# BASE_1.net
KiCad netlist of a schematic drawn in Altium Designer
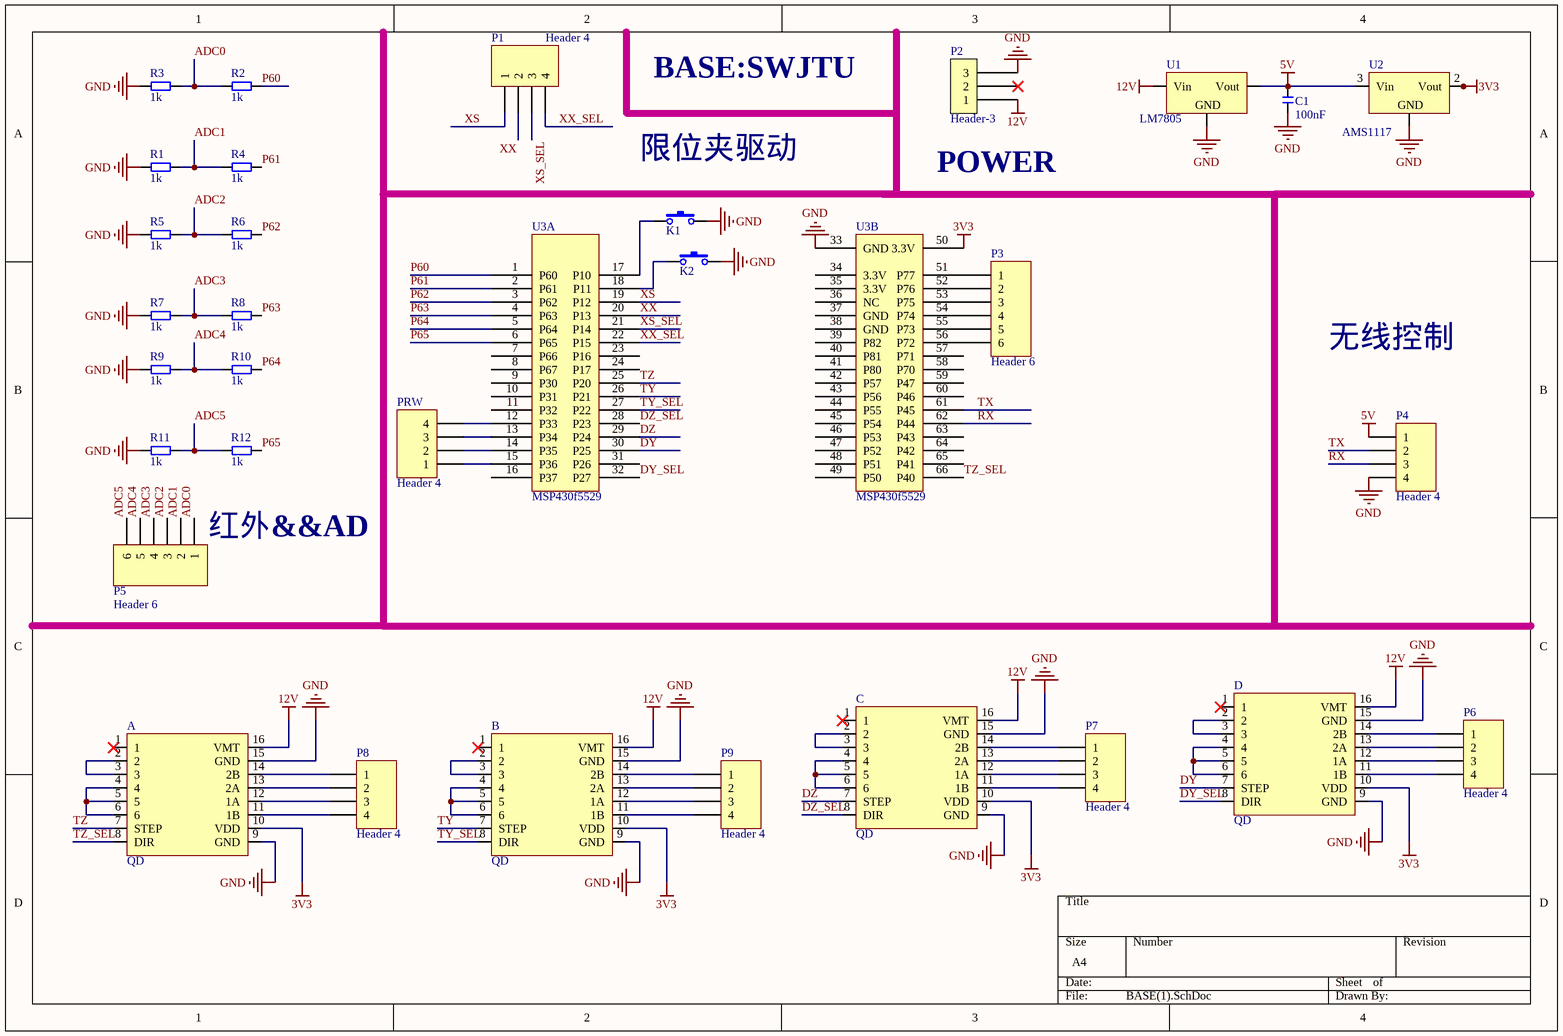
[diagram p0: BASE(1).SchDoc]

(export (version "E")
  (design (tool "Eeschema 10.0.6"))
  (components
    (comp (ref "A") (value "QD") (footprint "QD") (libsource (lib "QD") (part "QD")))
    (comp (ref "B") (value "QD") (footprint "QD") (libsource (lib "QD") (part "QD")))
    (comp (ref "C") (value "QD") (footprint "QD") (libsource (lib "QD") (part "QD")))
    (comp (ref "C1")
      (value "100nF")
      (footprint "lanfengdi:CAP-7.6")
      (description "无极电容")
      (libsource (lib "lanfengdi") (part "Cap"))
    )
    (comp (ref "D") (value "QD") (footprint "QD") (libsource (lib "QD") (part "QD")))
    (comp (ref "K1")
      (value "SW-PB")
      (footprint "lanfengdi:SW-4")
      (description "轻触开关")
      (libsource (lib "lanfengdi") (part "SW-PB"))
    )
    (comp (ref "K2")
      (value "SW-PB")
      (footprint "lanfengdi:SW-4")
      (description "轻触开关")
      (libsource (lib "lanfengdi") (part "SW-PB"))
    )
    (comp (ref "P1")
      (value "Header 4")
      (footprint "4PIN-2.54 A")
      (description "Header, 4-Pin")
      (fields (field (name "PUBLISHER") "Altium Limited"))
      (libsource (lib "") (part "Header 4_1"))
    )
    (comp (ref "P2")
      (value "Header-3")
      (footprint "terminal-03-3")
      (description "三针插座")
      (libsource (lib "Connection") (part "Header-3"))
    )
    (comp (ref "P3")
      (value "Header 6")
      (footprint "HDR1X6")
      (description "Header, 6-Pin")
      (fields (field (name "PUBLISHER") "Altium Limited"))
      (libsource (lib "") (part "Header 6_1"))
    )
    (comp (ref "P4")
      (value "Header 4")
      (footprint "4PIN-2.54 A")
      (description "Header, 4-Pin")
      (fields (field (name "PUBLISHER") "Altium Limited"))
      (libsource (lib "Miscellaneous Connectors") (part "Header 4"))
    )
    (comp (ref "P5")
      (value "Header 6")
      (footprint "HDR1X6")
      (description "Header, 6-Pin")
      (fields (field (name "PUBLISHER") "Altium Limited"))
      (libsource (lib "Miscellaneous Connectors") (part "Header 6"))
    )
    (comp (ref "P6")
      (value "Header 4")
      (footprint "4PIN-2.54 A")
      (description "Header, 4-Pin")
      (fields (field (name "PUBLISHER") "Altium Limited"))
      (libsource (lib "Miscellaneous Connectors") (part "Header 4"))
    )
    (comp (ref "P7")
      (value "Header 4")
      (footprint "4PIN-2.54 A")
      (description "Header, 4-Pin")
      (fields (field (name "PUBLISHER") "Altium Limited"))
      (libsource (lib "Miscellaneous Connectors") (part "Header 4"))
    )
    (comp (ref "P8")
      (value "Header 4")
      (footprint "4PIN-2.54 A")
      (description "Header, 4-Pin")
      (fields (field (name "PUBLISHER") "Altium Limited"))
      (libsource (lib "Miscellaneous Connectors") (part "Header 4"))
    )
    (comp (ref "P9")
      (value "Header 4")
      (footprint "4PIN-2.54 A")
      (description "Header, 4-Pin")
      (fields (field (name "PUBLISHER") "Altium Limited"))
      (libsource (lib "Miscellaneous Connectors") (part "Header 4"))
    )
    (comp (ref "PRW")
      (value "Header 4")
      (footprint "4PIN-2.54 A")
      (description "Header, 4-Pin")
      (fields (field (name "PUBLISHER") "Altium Limited"))
      (libsource (lib "") (part "Header 4_2"))
    )
    (comp (ref "R1")
      (value "1k")
      (footprint "Axial-0.3-7.62")
      (description "电阻  RES")
      (libsource (lib "lanfengdi") (part "RES"))
    )
    (comp (ref "R2")
      (value "1k")
      (footprint "lanfengdi:R0805")
      (description "电阻  RES")
      (libsource (lib "lanfengdi") (part "RES"))
    )
    (comp (ref "R3")
      (value "1k")
      (footprint "lanfengdi:R0805")
      (description "电阻  RES")
      (libsource (lib "lanfengdi") (part "RES"))
    )
    (comp (ref "R4")
      (value "1k")
      (footprint "lanfengdi:R0805")
      (description "电阻  RES")
      (libsource (lib "lanfengdi") (part "RES"))
    )
    (comp (ref "R5")
      (value "1k")
      (footprint "Axial-0.3-7.62")
      (description "电阻  RES")
      (libsource (lib "lanfengdi") (part "RES"))
    )
    (comp (ref "R6")
      (value "1k")
      (footprint "lanfengdi:R0805")
      (description "电阻  RES")
      (libsource (lib "lanfengdi") (part "RES"))
    )
    (comp (ref "R7")
      (value "1k")
      (footprint "Axial-0.3-7.62")
      (description "电阻  RES")
      (libsource (lib "lanfengdi") (part "RES"))
    )
    (comp (ref "R8")
      (value "1k")
      (footprint "lanfengdi:R0805")
      (description "电阻  RES")
      (libsource (lib "lanfengdi") (part "RES"))
    )
    (comp (ref "R9")
      (value "1k")
      (footprint "Axial-0.3-7.62")
      (description "电阻  RES")
      (libsource (lib "lanfengdi") (part "RES"))
    )
    (comp (ref "R10")
      (value "1k")
      (footprint "lanfengdi:R0805")
      (description "电阻  RES")
      (libsource (lib "lanfengdi") (part "RES"))
    )
    (comp (ref "R11")
      (value "1k")
      (footprint "lanfengdi:R0805")
      (description "电阻  RES")
      (libsource (lib "lanfengdi") (part "RES"))
    )
    (comp (ref "R12")
      (value "1k")
      (footprint "lanfengdi:R0805")
      (description "电阻  RES")
      (libsource (lib "lanfengdi") (part "RES"))
    )
    (comp (ref "U1")
      (value "LM7805")
      (footprint "lanfengdi:TO-220")
      (description "三端稳压器")
      (libsource (lib "lanfengdi") (part "LM78XX"))
    )
    (comp (ref "U2")
      (value "AMS1117")
      (footprint "lanfengdi:SOT-223")
      (description "LDO")
      (libsource (lib "lanfengdi") (part "AMS1117"))
    )
    (comp (ref "U3")
      (value "MSP430f5529")
      (footprint "msp430f5529")
      (libsource (lib "5529") (part "MSP430f5529"))
    )
  )
  (nets
    (net (code "1") (name "/ADC0") (class "Default")
      (node (ref "P5") (pin "1") (pinfunction "1_1") (pintype "passive"))
      (node (ref "R2") (pin "1") (pinfunction "1_1") (pintype "passive"))
      (node (ref "R3") (pin "2") (pinfunction "2_2") (pintype "passive"))
    )
    (net (code "2") (name "/ADC1") (class "Default")
      (node (ref "P5") (pin "2") (pinfunction "2_2") (pintype "passive"))
      (node (ref "R1") (pin "2") (pinfunction "2_2") (pintype "passive"))
      (node (ref "R4") (pin "1") (pinfunction "1_1") (pintype "passive"))
    )
    (net (code "3") (name "/ADC2") (class "Default")
      (node (ref "P5") (pin "3") (pinfunction "3_3") (pintype "passive"))
      (node (ref "R5") (pin "2") (pinfunction "2_2") (pintype "passive"))
      (node (ref "R6") (pin "1") (pinfunction "1_1") (pintype "passive"))
    )
    (net (code "4") (name "/ADC3") (class "Default")
      (node (ref "P5") (pin "4") (pinfunction "4_4") (pintype "passive"))
      (node (ref "R7") (pin "2") (pinfunction "2_2") (pintype "passive"))
      (node (ref "R8") (pin "1") (pinfunction "1_1") (pintype "passive"))
    )
    (net (code "5") (name "/ADC4") (class "Default")
      (node (ref "P5") (pin "5") (pinfunction "5_5") (pintype "passive"))
      (node (ref "R10") (pin "1") (pinfunction "1_1") (pintype "passive"))
      (node (ref "R9") (pin "2") (pinfunction "2_2") (pintype "passive"))
    )
    (net (code "6") (name "/ADC5") (class "Default")
      (node (ref "P5") (pin "6") (pinfunction "6_6") (pintype "passive"))
      (node (ref "R11") (pin "2") (pinfunction "2_2") (pintype "passive"))
      (node (ref "R12") (pin "1") (pinfunction "1_1") (pintype "passive"))
    )
    (net (code "7") (name "/DY") (class "Default")
      (node (ref "D") (pin "7") (pinfunction "STEP_7") (pintype "passive"))
      (node (ref "U3") (pin "30") (pinfunction "P25_30") (pintype "passive"))
    )
    (net (code "8") (name "/DY_SEL") (class "Default")
      (node (ref "D") (pin "8") (pinfunction "DIR_8") (pintype "passive"))
      (node (ref "U3") (pin "32") (pinfunction "P27_32") (pintype "passive"))
    )
    (net (code "9") (name "/DZ") (class "Default")
      (node (ref "C") (pin "7") (pinfunction "STEP_7") (pintype "passive"))
      (node (ref "U3") (pin "29") (pinfunction "P24_29") (pintype "passive"))
    )
    (net (code "10") (name "/DZ_SEL") (class "Default")
      (node (ref "C") (pin "8") (pinfunction "DIR_8") (pintype "passive"))
      (node (ref "U3") (pin "28") (pinfunction "P23_28") (pintype "passive"))
    )
    (net (code "11") (name "/P60") (class "Default")
      (node (ref "R2") (pin "2") (pinfunction "2_2") (pintype "passive"))
      (node (ref "U3") (pin "1") (pinfunction "P60_1") (pintype "passive"))
    )
    (net (code "12") (name "/P61") (class "Default")
      (node (ref "R4") (pin "2") (pinfunction "2_2") (pintype "passive"))
      (node (ref "U3") (pin "2") (pinfunction "P61_2") (pintype "passive"))
    )
    (net (code "13") (name "/P62") (class "Default")
      (node (ref "R6") (pin "2") (pinfunction "2_2") (pintype "passive"))
      (node (ref "U3") (pin "3") (pinfunction "P62_3") (pintype "passive"))
    )
    (net (code "14") (name "/P63") (class "Default")
      (node (ref "R8") (pin "2") (pinfunction "2_2") (pintype "passive"))
      (node (ref "U3") (pin "4") (pinfunction "P63_4") (pintype "passive"))
    )
    (net (code "15") (name "/P64") (class "Default")
      (node (ref "R10") (pin "2") (pinfunction "2_2") (pintype "passive"))
      (node (ref "U3") (pin "5") (pinfunction "P64_5") (pintype "passive"))
    )
    (net (code "16") (name "/P65") (class "Default")
      (node (ref "R12") (pin "2") (pinfunction "2_2") (pintype "passive"))
      (node (ref "U3") (pin "6") (pinfunction "P65_6") (pintype "passive"))
    )
    (net (code "17") (name "/RX") (class "Default")
      (node (ref "P4") (pin "3") (pinfunction "3_3") (pintype "passive"))
      (node (ref "U3") (pin "62") (pinfunction "P44_62") (pintype "passive"))
    )
    (net (code "18") (name "/TX") (class "Default")
      (node (ref "P4") (pin "2") (pinfunction "2_2") (pintype "passive"))
      (node (ref "U3") (pin "61") (pinfunction "P45_61") (pintype "passive"))
    )
    (net (code "19") (name "/TY") (class "Default")
      (node (ref "B") (pin "7") (pinfunction "STEP_7") (pintype "passive"))
      (node (ref "U3") (pin "26") (pinfunction "P21_26") (pintype "passive"))
    )
    (net (code "20") (name "/TY_SEL") (class "Default")
      (node (ref "B") (pin "8") (pinfunction "DIR_8") (pintype "passive"))
      (node (ref "U3") (pin "27") (pinfunction "P22_27") (pintype "passive"))
    )
    (net (code "21") (name "/TZ") (class "Default")
      (node (ref "A") (pin "7") (pinfunction "STEP_7") (pintype "passive"))
      (node (ref "U3") (pin "25") (pinfunction "P20_25") (pintype "passive"))
    )
    (net (code "22") (name "/TZ_SEL") (class "Default")
      (node (ref "A") (pin "8") (pinfunction "DIR_8") (pintype "passive"))
      (node (ref "U3") (pin "66") (pinfunction "P40_66") (pintype "passive"))
    )
    (net (code "23") (name "/XS") (class "Default")
      (node (ref "P1") (pin "1") (pinfunction "1_1") (pintype "passive"))
      (node (ref "U3") (pin "19") (pinfunction "P12_19") (pintype "passive"))
    )
    (net (code "24") (name "/XS_SEL") (class "Default")
      (node (ref "P1") (pin "3") (pinfunction "3_3") (pintype "passive"))
      (node (ref "U3") (pin "21") (pinfunction "P14_21") (pintype "passive"))
    )
    (net (code "25") (name "/XX") (class "Default")
      (node (ref "P1") (pin "2") (pinfunction "2_2") (pintype "passive"))
      (node (ref "U3") (pin "20") (pinfunction "P13_20") (pintype "passive"))
    )
    (net (code "26") (name "/XX_SEL") (class "Default")
      (node (ref "P1") (pin "4") (pinfunction "4_4") (pintype "passive"))
      (node (ref "U3") (pin "22") (pinfunction "P15_22") (pintype "passive"))
    )
    (net (code "27") (name "3V3") (class "Default")
      (node (ref "A") (pin "10") (pinfunction "VDD_10") (pintype "passive"))
      (node (ref "B") (pin "10") (pinfunction "VDD_10") (pintype "passive"))
      (node (ref "C") (pin "10") (pinfunction "VDD_10") (pintype "passive"))
      (node (ref "D") (pin "10") (pinfunction "VDD_10") (pintype "passive"))
      (node (ref "U2") (pin "2") (pinfunction "Vout_2") (pintype "passive"))
      (node (ref "U2") (pin "4") (pinfunction "Vout_4") (pintype "passive"))
      (node (ref "U3") (pin "50") (pinfunction "3.3V_50") (pintype "passive"))
    )
    (net (code "28") (name "5V") (class "Default")
      (node (ref "C1") (pin "2") (pinfunction "2_2") (pintype "passive"))
      (node (ref "P4") (pin "1") (pinfunction "1_1") (pintype "passive"))
      (node (ref "U1") (pin "3") (pinfunction "Vout_3") (pintype "passive"))
      (node (ref "U2") (pin "3") (pinfunction "Vin_3") (pintype "passive"))
    )
    (net (code "29") (name "12V") (class "Default")
      (node (ref "A") (pin "16") (pinfunction "VMT_16") (pintype "passive"))
      (node (ref "B") (pin "16") (pinfunction "VMT_16") (pintype "passive"))
      (node (ref "C") (pin "16") (pinfunction "VMT_16") (pintype "passive"))
      (node (ref "D") (pin "16") (pinfunction "VMT_16") (pintype "passive"))
      (node (ref "P2") (pin "1") (pinfunction "1_1") (pintype "passive"))
      (node (ref "U1") (pin "1") (pinfunction "Vin_1") (pintype "passive"))
    )
    (net (code "30") (name "GND") (class "Default")
      (node (ref "A") (pin "15") (pinfunction "GND_15") (pintype "passive"))
      (node (ref "A") (pin "9") (pinfunction "GND_9") (pintype "passive"))
      (node (ref "B") (pin "15") (pinfunction "GND_15") (pintype "passive"))
      (node (ref "B") (pin "9") (pinfunction "GND_9") (pintype "passive"))
      (node (ref "C") (pin "15") (pinfunction "GND_15") (pintype "passive"))
      (node (ref "C") (pin "9") (pinfunction "GND_9") (pintype "passive"))
      (node (ref "C1") (pin "1") (pinfunction "1_1") (pintype "passive"))
      (node (ref "D") (pin "15") (pinfunction "GND_15") (pintype "passive"))
      (node (ref "D") (pin "9") (pinfunction "GND_9") (pintype "passive"))
      (node (ref "K1") (pin "2") (pinfunction "2_2") (pintype "passive"))
      (node (ref "K2") (pin "2") (pinfunction "2_2") (pintype "passive"))
      (node (ref "P2") (pin "3") (pinfunction "3_3") (pintype "passive"))
      (node (ref "P4") (pin "4") (pinfunction "4_4") (pintype "passive"))
      (node (ref "R1") (pin "1") (pinfunction "1_1") (pintype "passive"))
      (node (ref "R11") (pin "1") (pinfunction "1_1") (pintype "passive"))
      (node (ref "R3") (pin "1") (pinfunction "1_1") (pintype "passive"))
      (node (ref "R5") (pin "1") (pinfunction "1_1") (pintype "passive"))
      (node (ref "R7") (pin "1") (pinfunction "1_1") (pintype "passive"))
      (node (ref "R9") (pin "1") (pinfunction "1_1") (pintype "passive"))
      (node (ref "U1") (pin "2") (pinfunction "GND_2") (pintype "passive"))
      (node (ref "U2") (pin "1") (pinfunction "GND_1") (pintype "passive"))
      (node (ref "U3") (pin "33") (pinfunction "GND_33") (pintype "passive"))
    )
    (net (code "31") (name "Net-(A-1A)") (class "Default")
      (node (ref "A") (pin "12") (pinfunction "1A_12") (pintype "passive"))
      (node (ref "P8") (pin "3") (pinfunction "3_3") (pintype "passive"))
    )
    (net (code "32") (name "Net-(A-1B)") (class "Default")
      (node (ref "A") (pin "11") (pinfunction "1B_11") (pintype "passive"))
      (node (ref "P8") (pin "4") (pinfunction "4_4") (pintype "passive"))
    )
    (net (code "33") (name "Net-(A-2A)") (class "Default")
      (node (ref "A") (pin "13") (pinfunction "2A_13") (pintype "passive"))
      (node (ref "P8") (pin "2") (pinfunction "2_2") (pintype "passive"))
    )
    (net (code "34") (name "Net-(A-2B)") (class "Default")
      (node (ref "A") (pin "14") (pinfunction "2B_14") (pintype "passive"))
      (node (ref "P8") (pin "1") (pinfunction "1_1") (pintype "passive"))
    )
    (net (code "35") (name "Net-(A-Pad2)") (class "Default")
      (node (ref "A") (pin "2") (pinfunction "2_2") (pintype "passive"))
      (node (ref "A") (pin "3") (pinfunction "3_3") (pintype "passive"))
    )
    (net (code "36") (name "Net-(A-Pad4)") (class "Default")
      (node (ref "A") (pin "4") (pinfunction "4_4") (pintype "passive"))
      (node (ref "A") (pin "5") (pinfunction "5_5") (pintype "passive"))
      (node (ref "A") (pin "6") (pinfunction "6_6") (pintype "passive"))
    )
    (net (code "37") (name "Net-(B-1A)") (class "Default")
      (node (ref "B") (pin "12") (pinfunction "1A_12") (pintype "passive"))
      (node (ref "P9") (pin "3") (pinfunction "3_3") (pintype "passive"))
    )
    (net (code "38") (name "Net-(B-1B)") (class "Default")
      (node (ref "B") (pin "11") (pinfunction "1B_11") (pintype "passive"))
      (node (ref "P9") (pin "4") (pinfunction "4_4") (pintype "passive"))
    )
    (net (code "39") (name "Net-(B-2A)") (class "Default")
      (node (ref "B") (pin "13") (pinfunction "2A_13") (pintype "passive"))
      (node (ref "P9") (pin "2") (pinfunction "2_2") (pintype "passive"))
    )
    (net (code "40") (name "Net-(B-2B)") (class "Default")
      (node (ref "B") (pin "14") (pinfunction "2B_14") (pintype "passive"))
      (node (ref "P9") (pin "1") (pinfunction "1_1") (pintype "passive"))
    )
    (net (code "41") (name "Net-(B-Pad2)") (class "Default")
      (node (ref "B") (pin "2") (pinfunction "2_2") (pintype "passive"))
      (node (ref "B") (pin "3") (pinfunction "3_3") (pintype "passive"))
    )
    (net (code "42") (name "Net-(B-Pad4)") (class "Default")
      (node (ref "B") (pin "4") (pinfunction "4_4") (pintype "passive"))
      (node (ref "B") (pin "5") (pinfunction "5_5") (pintype "passive"))
      (node (ref "B") (pin "6") (pinfunction "6_6") (pintype "passive"))
    )
    (net (code "43") (name "Net-(C-1A)") (class "Default")
      (node (ref "C") (pin "12") (pinfunction "1A_12") (pintype "passive"))
      (node (ref "P7") (pin "3") (pinfunction "3_3") (pintype "passive"))
    )
    (net (code "44") (name "Net-(C-1B)") (class "Default")
      (node (ref "C") (pin "11") (pinfunction "1B_11") (pintype "passive"))
      (node (ref "P7") (pin "4") (pinfunction "4_4") (pintype "passive"))
    )
    (net (code "45") (name "Net-(C-2A)") (class "Default")
      (node (ref "C") (pin "13") (pinfunction "2A_13") (pintype "passive"))
      (node (ref "P7") (pin "2") (pinfunction "2_2") (pintype "passive"))
    )
    (net (code "46") (name "Net-(C-2B)") (class "Default")
      (node (ref "C") (pin "14") (pinfunction "2B_14") (pintype "passive"))
      (node (ref "P7") (pin "1") (pinfunction "1_1") (pintype "passive"))
    )
    (net (code "47") (name "Net-(C-Pad2)") (class "Default")
      (node (ref "C") (pin "2") (pinfunction "2_2") (pintype "passive"))
      (node (ref "C") (pin "3") (pinfunction "3_3") (pintype "passive"))
    )
    (net (code "48") (name "Net-(C-Pad4)") (class "Default")
      (node (ref "C") (pin "4") (pinfunction "4_4") (pintype "passive"))
      (node (ref "C") (pin "5") (pinfunction "5_5") (pintype "passive"))
      (node (ref "C") (pin "6") (pinfunction "6_6") (pintype "passive"))
    )
    (net (code "49") (name "Net-(D-1A)") (class "Default")
      (node (ref "D") (pin "12") (pinfunction "1A_12") (pintype "passive"))
      (node (ref "P6") (pin "3") (pinfunction "3_3") (pintype "passive"))
    )
    (net (code "50") (name "Net-(D-1B)") (class "Default")
      (node (ref "D") (pin "11") (pinfunction "1B_11") (pintype "passive"))
      (node (ref "P6") (pin "4") (pinfunction "4_4") (pintype "passive"))
    )
    (net (code "51") (name "Net-(D-2A)") (class "Default")
      (node (ref "D") (pin "13") (pinfunction "2A_13") (pintype "passive"))
      (node (ref "P6") (pin "2") (pinfunction "2_2") (pintype "passive"))
    )
    (net (code "52") (name "Net-(D-2B)") (class "Default")
      (node (ref "D") (pin "14") (pinfunction "2B_14") (pintype "passive"))
      (node (ref "P6") (pin "1") (pinfunction "1_1") (pintype "passive"))
    )
    (net (code "53") (name "Net-(D-Pad2)") (class "Default")
      (node (ref "D") (pin "2") (pinfunction "2_2") (pintype "passive"))
      (node (ref "D") (pin "3") (pinfunction "3_3") (pintype "passive"))
    )
    (net (code "54") (name "Net-(D-Pad4)") (class "Default")
      (node (ref "D") (pin "4") (pinfunction "4_4") (pintype "passive"))
      (node (ref "D") (pin "5") (pinfunction "5_5") (pintype "passive"))
      (node (ref "D") (pin "6") (pinfunction "6_6") (pintype "passive"))
    )
    (net (code "55") (name "Net-(U3A-P10)") (class "Default")
      (node (ref "K1") (pin "1") (pinfunction "1_1") (pintype "passive"))
      (node (ref "U3") (pin "17") (pinfunction "P10_17") (pintype "passive"))
    )
    (net (code "56") (name "Net-(U3A-P11)") (class "Default")
      (node (ref "K2") (pin "1") (pinfunction "1_1") (pintype "passive"))
      (node (ref "U3") (pin "18") (pinfunction "P11_18") (pintype "passive"))
    )
    (net (code "57") (name "Net-(U3A-P33)") (class "Default")
      (node (ref "PRW") (pin "4") (pinfunction "4_4") (pintype "passive"))
      (node (ref "U3") (pin "12") (pinfunction "P33_12") (pintype "passive"))
    )
    (net (code "58") (name "Net-(U3A-P34)") (class "Default")
      (node (ref "PRW") (pin "3") (pinfunction "3_3") (pintype "passive"))
      (node (ref "U3") (pin "13") (pinfunction "P34_13") (pintype "passive"))
    )
    (net (code "59") (name "Net-(U3A-P35)") (class "Default")
      (node (ref "PRW") (pin "2") (pinfunction "2_2") (pintype "passive"))
      (node (ref "U3") (pin "14") (pinfunction "P35_14") (pintype "passive"))
    )
    (net (code "60") (name "Net-(U3A-P36)") (class "Default")
      (node (ref "PRW") (pin "1") (pinfunction "1_1") (pintype "passive"))
      (node (ref "U3") (pin "15") (pinfunction "P36_15") (pintype "passive"))
    )
    (net (code "61") (name "Net-(U3B-P72)") (class "Default")
      (node (ref "P3") (pin "6") (pinfunction "6_6") (pintype "passive"))
      (node (ref "U3") (pin "56") (pinfunction "P72_56") (pintype "passive"))
    )
    (net (code "62") (name "Net-(U3B-P73)") (class "Default")
      (node (ref "P3") (pin "5") (pinfunction "5_5") (pintype "passive"))
      (node (ref "U3") (pin "55") (pinfunction "P73_55") (pintype "passive"))
    )
    (net (code "63") (name "Net-(U3B-P74)") (class "Default")
      (node (ref "P3") (pin "4") (pinfunction "4_4") (pintype "passive"))
      (node (ref "U3") (pin "54") (pinfunction "P74_54") (pintype "passive"))
    )
    (net (code "64") (name "Net-(U3B-P75)") (class "Default")
      (node (ref "P3") (pin "3") (pinfunction "3_3") (pintype "passive"))
      (node (ref "U3") (pin "53") (pinfunction "P75_53") (pintype "passive"))
    )
    (net (code "65") (name "Net-(U3B-P76)") (class "Default")
      (node (ref "P3") (pin "2") (pinfunction "2_2") (pintype "passive"))
      (node (ref "U3") (pin "52") (pinfunction "P76_52") (pintype "passive"))
    )
    (net (code "66") (name "Net-(U3B-P77)") (class "Default")
      (node (ref "P3") (pin "1") (pinfunction "1_1") (pintype "passive"))
      (node (ref "U3") (pin "51") (pinfunction "P77_51") (pintype "passive"))
    )
    (net (code "67") (name "unconnected-(A-Pad1)") (class "Default")
      (node (ref "A") (pin "1") (pinfunction "1_1") (pintype "passive+no_connect"))
    )
    (net (code "68") (name "unconnected-(B-Pad1)") (class "Default")
      (node (ref "B") (pin "1") (pinfunction "1_1") (pintype "passive+no_connect"))
    )
    (net (code "69") (name "unconnected-(C-Pad1)") (class "Default")
      (node (ref "C") (pin "1") (pinfunction "1_1") (pintype "passive+no_connect"))
    )
    (net (code "70") (name "unconnected-(D-Pad1)") (class "Default")
      (node (ref "D") (pin "1") (pinfunction "1_1") (pintype "passive+no_connect"))
    )
    (net (code "71") (name "unconnected-(P2-Pad2)") (class "Default")
      (node (ref "P2") (pin "2") (pinfunction "2_2") (pintype "passive+no_connect"))
    )
    (net (code "72") (name "unconnected-(U3A-P16-Pad23)") (class "Default")
      (node (ref "U3") (pin "23") (pinfunction "P16_23") (pintype "passive"))
    )
    (net (code "73") (name "unconnected-(U3A-P17-Pad24)") (class "Default")
      (node (ref "U3") (pin "24") (pinfunction "P17_24") (pintype "passive"))
    )
    (net (code "74") (name "unconnected-(U3A-P26-Pad31)") (class "Default")
      (node (ref "U3") (pin "31") (pinfunction "P26_31") (pintype "passive"))
    )
    (net (code "75") (name "unconnected-(U3A-P30-Pad9)") (class "Default")
      (node (ref "U3") (pin "9") (pinfunction "P30_9") (pintype "passive"))
    )
    (net (code "76") (name "unconnected-(U3A-P31-Pad10)") (class "Default")
      (node (ref "U3") (pin "10") (pinfunction "P31_10") (pintype "passive"))
    )
    (net (code "77") (name "unconnected-(U3A-P32-Pad11)") (class "Default")
      (node (ref "U3") (pin "11") (pinfunction "P32_11") (pintype "passive"))
    )
    (net (code "78") (name "unconnected-(U3A-P37-Pad16)") (class "Default")
      (node (ref "U3") (pin "16") (pinfunction "P37_16") (pintype "passive"))
    )
    (net (code "79") (name "unconnected-(U3A-P66-Pad7)") (class "Default")
      (node (ref "U3") (pin "7") (pinfunction "P66_7") (pintype "passive"))
    )
    (net (code "80") (name "unconnected-(U3A-P67-Pad8)") (class "Default")
      (node (ref "U3") (pin "8") (pinfunction "P67_8") (pintype "passive"))
    )
    (net (code "81") (name "unconnected-(U3B-3.3V-Pad34)") (class "Default")
      (node (ref "U3") (pin "34") (pinfunction "3.3V_34") (pintype "passive"))
    )
    (net (code "82") (name "unconnected-(U3B-3.3V-Pad35)") (class "Default")
      (node (ref "U3") (pin "35") (pinfunction "3.3V_35") (pintype "passive"))
    )
    (net (code "83") (name "unconnected-(U3B-GND-Pad37)") (class "Default")
      (node (ref "U3") (pin "37") (pinfunction "GND_37") (pintype "passive"))
    )
    (net (code "84") (name "unconnected-(U3B-GND-Pad38)") (class "Default")
      (node (ref "U3") (pin "38") (pinfunction "GND_38") (pintype "passive"))
    )
    (net (code "85") (name "unconnected-(U3B-NC-Pad36)") (class "Default")
      (node (ref "U3") (pin "36") (pinfunction "NC_36") (pintype "passive"))
    )
    (net (code "86") (name "unconnected-(U3B-P41-Pad65)") (class "Default")
      (node (ref "U3") (pin "65") (pinfunction "P41_65") (pintype "passive"))
    )
    (net (code "87") (name "unconnected-(U3B-P42-Pad64)") (class "Default")
      (node (ref "U3") (pin "64") (pinfunction "P42_64") (pintype "passive"))
    )
    (net (code "88") (name "unconnected-(U3B-P43-Pad63)") (class "Default")
      (node (ref "U3") (pin "63") (pinfunction "P43_63") (pintype "passive"))
    )
    (net (code "89") (name "unconnected-(U3B-P46-Pad60)") (class "Default")
      (node (ref "U3") (pin "60") (pinfunction "P46_60") (pintype "passive"))
    )
    (net (code "90") (name "unconnected-(U3B-P47-Pad59)") (class "Default")
      (node (ref "U3") (pin "59") (pinfunction "P47_59") (pintype "passive"))
    )
    (net (code "91") (name "unconnected-(U3B-P50-Pad49)") (class "Default")
      (node (ref "U3") (pin "49") (pinfunction "P50_49") (pintype "passive"))
    )
    (net (code "92") (name "unconnected-(U3B-P51-Pad48)") (class "Default")
      (node (ref "U3") (pin "48") (pinfunction "P51_48") (pintype "passive"))
    )
    (net (code "93") (name "unconnected-(U3B-P52-Pad47)") (class "Default")
      (node (ref "U3") (pin "47") (pinfunction "P52_47") (pintype "passive"))
    )
    (net (code "94") (name "unconnected-(U3B-P53-Pad46)") (class "Default")
      (node (ref "U3") (pin "46") (pinfunction "P53_46") (pintype "passive"))
    )
    (net (code "95") (name "unconnected-(U3B-P54-Pad45)") (class "Default")
      (node (ref "U3") (pin "45") (pinfunction "P54_45") (pintype "passive"))
    )
    (net (code "96") (name "unconnected-(U3B-P55-Pad44)") (class "Default")
      (node (ref "U3") (pin "44") (pinfunction "P55_44") (pintype "passive"))
    )
    (net (code "97") (name "unconnected-(U3B-P56-Pad43)") (class "Default")
      (node (ref "U3") (pin "43") (pinfunction "P56_43") (pintype "passive"))
    )
    (net (code "98") (name "unconnected-(U3B-P57-Pad42)") (class "Default")
      (node (ref "U3") (pin "42") (pinfunction "P57_42") (pintype "passive"))
    )
    (net (code "99") (name "unconnected-(U3B-P70-Pad58)") (class "Default")
      (node (ref "U3") (pin "58") (pinfunction "P70_58") (pintype "passive"))
    )
    (net (code "100") (name "unconnected-(U3B-P71-Pad57)") (class "Default")
      (node (ref "U3") (pin "57") (pinfunction "P71_57") (pintype "passive"))
    )
    (net (code "101") (name "unconnected-(U3B-P80-Pad41)") (class "Default")
      (node (ref "U3") (pin "41") (pinfunction "P80_41") (pintype "passive"))
    )
    (net (code "102") (name "unconnected-(U3B-P81-Pad40)") (class "Default")
      (node (ref "U3") (pin "40") (pinfunction "P81_40") (pintype "passive"))
    )
    (net (code "103") (name "unconnected-(U3B-P82-Pad39)") (class "Default")
      (node (ref "U3") (pin "39") (pinfunction "P82_39") (pintype "passive"))
    )
  )
)
